# PowerTestbenchBoard.net
KiCad netlist of a schematic drawn in EAGLE
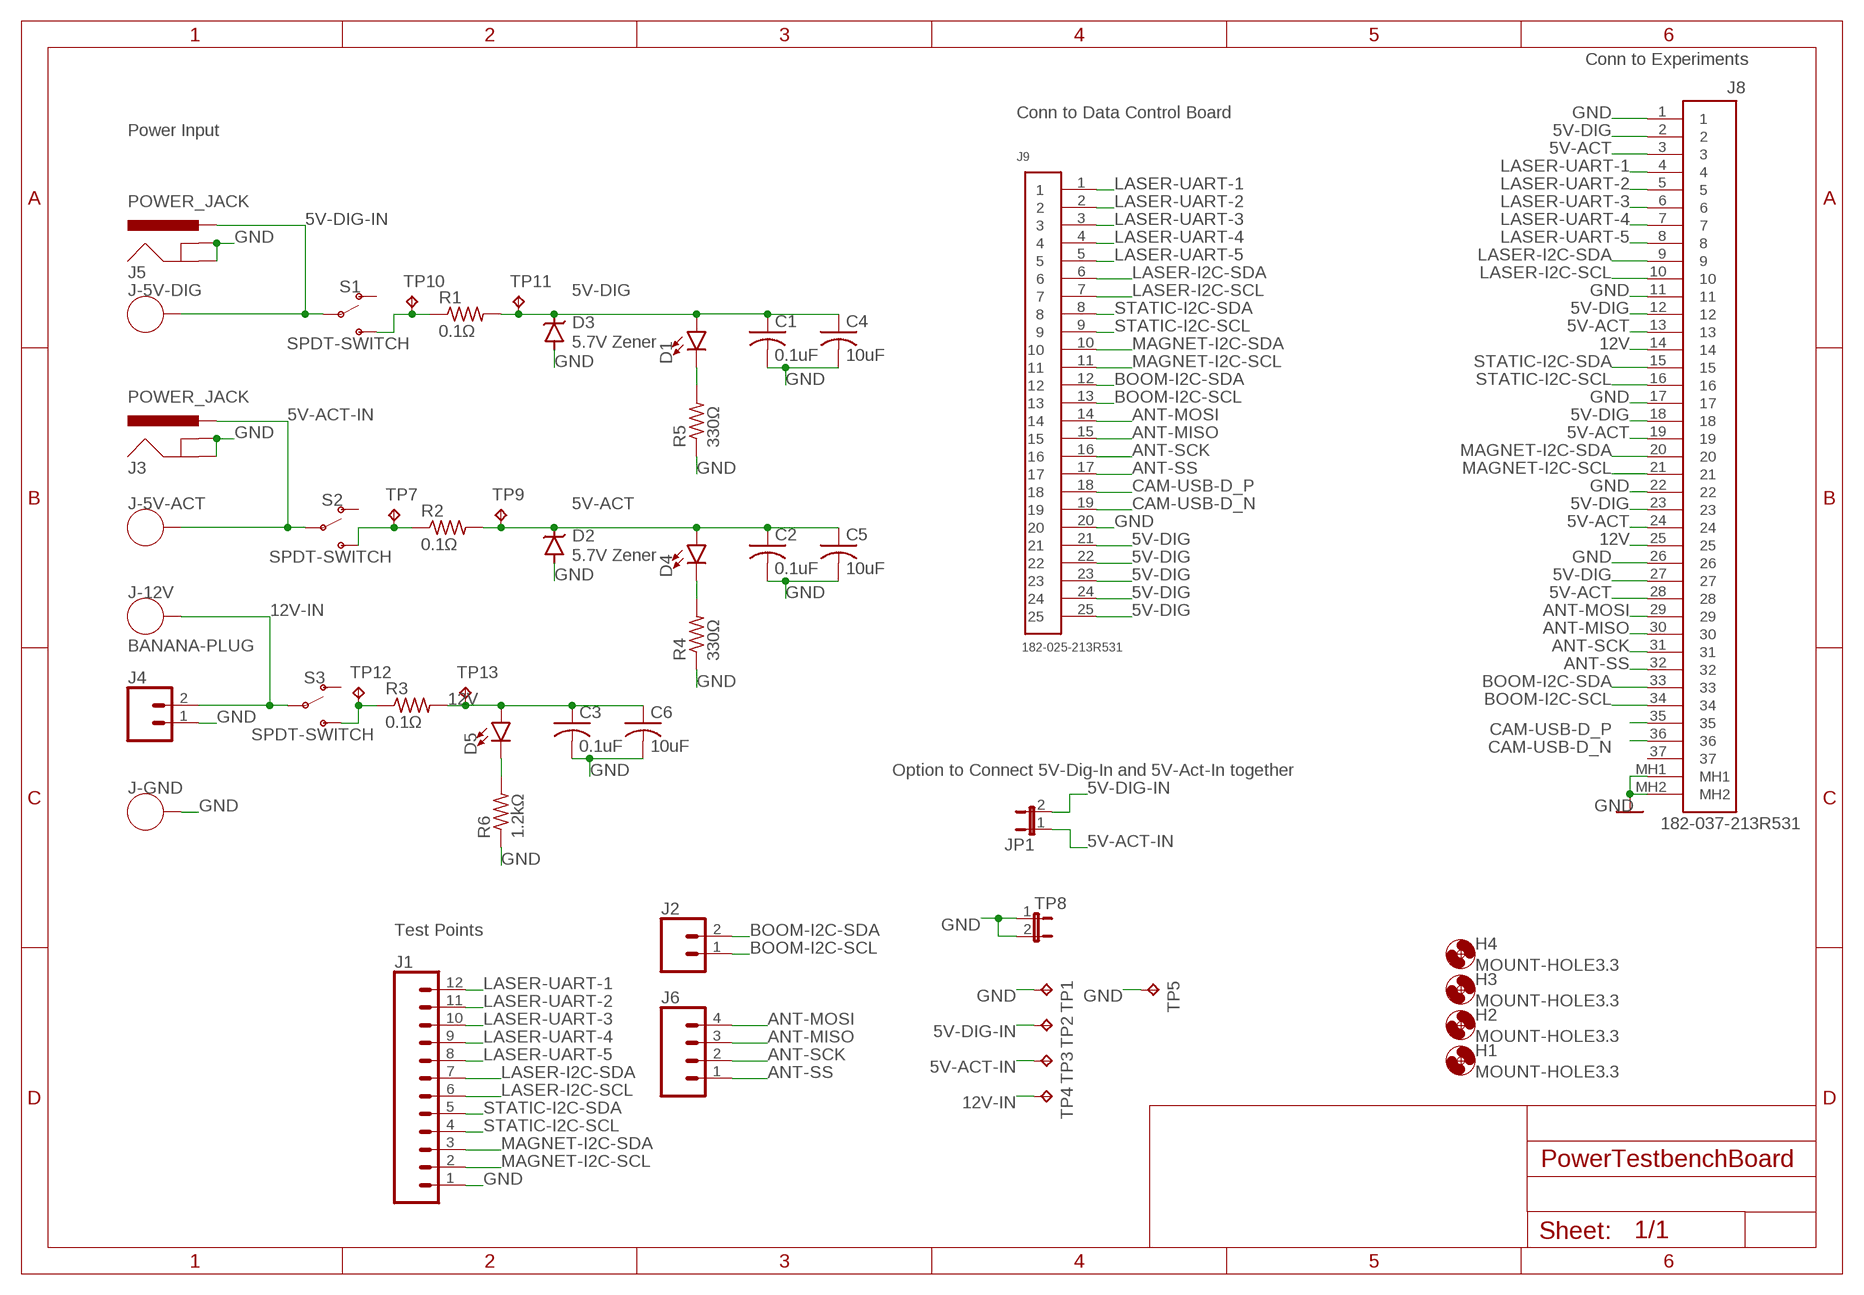
[diagram p0: schematic, sheet 1]

(export (version "E")
  (design (tool "Eeschema 10.0.6"))
  (components
    (comp (ref "C1")
      (value "0.1uF")
      (footprint "eagle-import:C0805")
      (libsource (lib "eagle-import") (part "C-USC0805"))
    )
    (comp (ref "C2")
      (value "0.1uF")
      (footprint "eagle-import:C0805")
      (libsource (lib "eagle-import") (part "C-USC0805"))
    )
    (comp (ref "C3")
      (value "0.1uF")
      (footprint "eagle-import:C0805")
      (libsource (lib "eagle-import") (part "C-USC0805"))
    )
    (comp (ref "C4")
      (value "10uF")
      (footprint "eagle-import:C0805")
      (libsource (lib "eagle-import") (part "C-USC0805"))
    )
    (comp (ref "C5")
      (value "10uF")
      (footprint "eagle-import:C0805")
      (libsource (lib "eagle-import") (part "C-USC0805"))
    )
    (comp (ref "C6")
      (value "10uF")
      (footprint "eagle-import:C0805")
      (libsource (lib "eagle-import") (part "C-USC0805"))
    )
    (comp (ref "D1")
      (value "LED-3MM-NO_SILK")
      (footprint "eagle-import:LED_3MM-NS")
      (libsource (lib "eagle-import") (part "LED-3MM-NO_SILK"))
    )
    (comp (ref "D2")
      (value "5.7V Zener")
      (footprint "eagle-import:SMB")
      (libsource (lib "eagle-import") (part "ZENER-GENERICSMB"))
    )
    (comp (ref "D3")
      (value "5.7V Zener")
      (footprint "eagle-import:SMB")
      (libsource (lib "eagle-import") (part "ZENER-GENERICSMB"))
    )
    (comp (ref "D4")
      (value "LED-3MM-NO_SILK")
      (footprint "eagle-import:LED_3MM-NS")
      (libsource (lib "eagle-import") (part "LED-3MM-NO_SILK"))
    )
    (comp (ref "D5")
      (value "LED-3MM-NO_SILK")
      (footprint "eagle-import:LED_3MM-NS")
      (libsource (lib "eagle-import") (part "LED-3MM-NO_SILK"))
    )
    (comp (ref "H1")
      (value "MOUNT-HOLE3.3")
      (footprint "eagle-import:3,3")
      (libsource (lib "eagle-import") (part "MOUNT-HOLE3.3"))
    )
    (comp (ref "H2")
      (value "MOUNT-HOLE3.3")
      (footprint "eagle-import:3,3")
      (libsource (lib "eagle-import") (part "MOUNT-HOLE3.3"))
    )
    (comp (ref "H3")
      (value "MOUNT-HOLE3.3")
      (footprint "eagle-import:3,3")
      (libsource (lib "eagle-import") (part "MOUNT-HOLE3.3"))
    )
    (comp (ref "H4")
      (value "MOUNT-HOLE3.3")
      (footprint "eagle-import:3,3")
      (libsource (lib "eagle-import") (part "MOUNT-HOLE3.3"))
    )
    (comp (ref "J-5V-ACT")
      (value "BANANA-PLUG")
      (footprint "eagle-import:BANANA-JACK")
      (libsource (lib "eagle-import") (part "BANANA-PLUG"))
    )
    (comp (ref "J-5V-DIG")
      (value "BANANA-PLUG")
      (footprint "eagle-import:BANANA-JACK")
      (libsource (lib "eagle-import") (part "BANANA-PLUG"))
    )
    (comp (ref "J-12V")
      (value "BANANA-PLUG")
      (footprint "eagle-import:BANANA-JACK")
      (libsource (lib "eagle-import") (part "BANANA-PLUG"))
    )
    (comp (ref "J-GND")
      (value "BANANA-PLUG")
      (footprint "eagle-import:BANANA-JACK")
      (libsource (lib "eagle-import") (part "BANANA-PLUG"))
    )
    (comp (ref "J1")
      (value "CONN_12")
      (footprint "eagle-import:1X12")
      (libsource (lib "eagle-import") (part "CONN_12"))
    )
    (comp (ref "J2")
      (value "CONN_02")
      (footprint "eagle-import:1X02")
      (libsource (lib "eagle-import") (part "CONN_02"))
    )
    (comp (ref "J3")
      (value "POWER_JACK")
      (footprint "eagle-import:POWER_JACK_PTH")
      (libsource (lib "eagle-import") (part "POWER_JACK"))
    )
    (comp (ref "J4")
      (value "CONN_023.5MM")
      (footprint "eagle-import:SCREWTERMINAL-3.5MM-2")
      (libsource (lib "eagle-import") (part "CONN_023.5MM"))
    )
    (comp (ref "J5")
      (value "POWER_JACK")
      (footprint "eagle-import:POWER_JACK_PTH")
      (libsource (lib "eagle-import") (part "POWER_JACK"))
    )
    (comp (ref "J6")
      (value "CONN_04")
      (footprint "eagle-import:1X04")
      (libsource (lib "eagle-import") (part "CONN_04"))
    )
    (comp (ref "J8")
      (value "182-037-213R531")
      (footprint "eagle-import:182-037-213R531")
      (fields
        (field (name "DIGI_KEY_PART_NUMBER") "182-37FE-ND")
        (field (name "MANUFACTURER") "NorComp Inc.")
        (field (name "CREATED_BY") "PCBLayout.com")
      )
      (libsource (lib "eagle-import") (part "182-037-213R531"))
    )
    (comp (ref "J9")
      (value "182-025-213R531")
      (footprint "eagle-import:182-025-213R531")
      (fields
        (field (name "DIGIKEY_PART_NO") "182-25FE-ND")
        (field (name "MANUFACTURER") "NorComp Inc.")
        (field (name "CREATED_BY") "PCBLayout.com")
      )
      (libsource (lib "eagle-import") (part "182-025-213R531"))
    )
    (comp (ref "JP1")
      (value "JP1E")
      (footprint "eagle-import:JP1")
      (libsource (lib "eagle-import") (part "JP1E"))
    )
    (comp (ref "R1")
      (value "0.1Ω")
      (footprint "eagle-import:R1206")
      (libsource (lib "eagle-import") (part "R-US_R1206"))
    )
    (comp (ref "R2")
      (value "0.1Ω")
      (footprint "eagle-import:R1206")
      (libsource (lib "eagle-import") (part "R-US_R1206"))
    )
    (comp (ref "R3")
      (value "0.1Ω")
      (footprint "eagle-import:R1206")
      (libsource (lib "eagle-import") (part "R-US_R1206"))
    )
    (comp (ref "R4")
      (value "330Ω")
      (footprint "eagle-import:R0805")
      (libsource (lib "eagle-import") (part "R-US_R0805"))
    )
    (comp (ref "R5")
      (value "330Ω")
      (footprint "eagle-import:R0805")
      (libsource (lib "eagle-import") (part "R-US_R0805"))
    )
    (comp (ref "R6")
      (value "1.2kΩ")
      (footprint "eagle-import:R0805")
      (libsource (lib "eagle-import") (part "R-US_R0805"))
    )
    (comp (ref "S1")
      (value "SPDT-SWITCH")
      (footprint "eagle-import:SWITCH_SPDT_PTH_11.6X4.0MM")
      (libsource (lib "eagle-import") (part "SPDT-SWITCH"))
    )
    (comp (ref "S2")
      (value "SPDT-SWITCH")
      (footprint "eagle-import:SWITCH_SPDT_PTH_11.6X4.0MM")
      (libsource (lib "eagle-import") (part "SPDT-SWITCH"))
    )
    (comp (ref "S3")
      (value "SPDT-SWITCH")
      (footprint "eagle-import:SWITCH_SPDT_PTH_11.6X4.0MM")
      (libsource (lib "eagle-import") (part "SPDT-SWITCH"))
    )
    (comp (ref "TP1")
      (value "TPPAD1-13")
      (footprint "eagle-import:P1-13")
      (libsource (lib "eagle-import") (part "TPPAD1-13"))
    )
    (comp (ref "TP2")
      (value "TPPAD1-13")
      (footprint "eagle-import:P1-13")
      (libsource (lib "eagle-import") (part "TPPAD1-13"))
    )
    (comp (ref "TP3")
      (value "TPPAD1-13")
      (footprint "eagle-import:P1-13")
      (libsource (lib "eagle-import") (part "TPPAD1-13"))
    )
    (comp (ref "TP4")
      (value "TPPAD1-13")
      (footprint "eagle-import:P1-13")
      (libsource (lib "eagle-import") (part "TPPAD1-13"))
    )
    (comp (ref "TP5")
      (value "TPPAD1-13")
      (footprint "eagle-import:P1-13")
      (libsource (lib "eagle-import") (part "TPPAD1-13"))
    )
    (comp (ref "TP7")
      (value "TPPAD1-13")
      (footprint "eagle-import:P1-13")
      (libsource (lib "eagle-import") (part "TPPAD1-13"))
    )
    (comp (ref "TP8")
      (value "JP1E")
      (footprint "eagle-import:JP1")
      (libsource (lib "eagle-import") (part "JP1E"))
    )
    (comp (ref "TP9")
      (value "TPPAD1-13")
      (footprint "eagle-import:P1-13")
      (libsource (lib "eagle-import") (part "TPPAD1-13"))
    )
    (comp (ref "TP10")
      (value "TPPAD1-13")
      (footprint "eagle-import:P1-13")
      (libsource (lib "eagle-import") (part "TPPAD1-13"))
    )
    (comp (ref "TP11")
      (value "TPPAD1-13")
      (footprint "eagle-import:P1-13")
      (libsource (lib "eagle-import") (part "TPPAD1-13"))
    )
    (comp (ref "TP12")
      (value "TPPAD1-13")
      (footprint "eagle-import:P1-13")
      (libsource (lib "eagle-import") (part "TPPAD1-13"))
    )
    (comp (ref "TP13")
      (value "TPPAD1-13")
      (footprint "eagle-import:P1-13")
      (libsource (lib "eagle-import") (part "TPPAD1-13"))
    )
  )
  (nets
    (net (code "1") (name "/5V-ACT") (class "Default")
      (node (ref "C2") (pin "1") (pinfunction "1_1") (pintype "passive"))
      (node (ref "C5") (pin "1") (pinfunction "1_1") (pintype "passive"))
      (node (ref "D2") (pin "C") (pinfunction "C_C") (pintype "passive"))
      (node (ref "D4") (pin "A") (pinfunction "A_A") (pintype "passive"))
      (node (ref "J8") (pin "13") (pinfunction "13_13") (pintype "passive"))
      (node (ref "J8") (pin "19") (pinfunction "19_19") (pintype "passive"))
      (node (ref "J8") (pin "24") (pinfunction "24_24") (pintype "passive"))
      (node (ref "J8") (pin "28") (pinfunction "28_28") (pintype "passive"))
      (node (ref "J8") (pin "3") (pinfunction "3_3") (pintype "passive"))
      (node (ref "R2") (pin "2") (pinfunction "2_2") (pintype "passive"))
      (node (ref "TP9") (pin "TP") (pinfunction "TP_TP") (pintype "input"))
    )
    (net (code "2") (name "/5V-ACT-IN") (class "Default")
      (node (ref "J-5V-ACT") (pin "P$1") (pinfunction "P$1_P$1") (pintype "bidirectional"))
      (node (ref "J-5V-ACT") (pin "P$2") (pinfunction "P$1_P$2") (pintype "bidirectional"))
      (node (ref "J3") (pin "PWR") (pinfunction "PWR_PWR") (pintype "bidirectional"))
      (node (ref "JP1") (pin "1") (pinfunction "1_1") (pintype "passive"))
      (node (ref "S2") (pin "2") (pinfunction "P_2") (pintype "passive"))
      (node (ref "TP3") (pin "TP") (pinfunction "TP_TP") (pintype "input"))
    )
    (net (code "3") (name "/5V-DIG") (class "Default")
      (node (ref "C1") (pin "1") (pinfunction "1_1") (pintype "passive"))
      (node (ref "C4") (pin "1") (pinfunction "1_1") (pintype "passive"))
      (node (ref "D1") (pin "A") (pinfunction "A_A") (pintype "passive"))
      (node (ref "D3") (pin "C") (pinfunction "C_C") (pintype "passive"))
      (node (ref "J8") (pin "12") (pinfunction "12_12") (pintype "passive"))
      (node (ref "J8") (pin "18") (pinfunction "18_18") (pintype "passive"))
      (node (ref "J8") (pin "2") (pinfunction "2_2") (pintype "passive"))
      (node (ref "J8") (pin "23") (pinfunction "23_23") (pintype "passive"))
      (node (ref "J8") (pin "27") (pinfunction "27_27") (pintype "passive"))
      (node (ref "J9") (pin "21") (pinfunction "21_21") (pintype "passive"))
      (node (ref "J9") (pin "22") (pinfunction "22_22") (pintype "passive"))
      (node (ref "J9") (pin "23") (pinfunction "23_23") (pintype "passive"))
      (node (ref "J9") (pin "24") (pinfunction "24_24") (pintype "passive"))
      (node (ref "J9") (pin "25") (pinfunction "25_25") (pintype "passive"))
      (node (ref "R1") (pin "2") (pinfunction "2_2") (pintype "passive"))
      (node (ref "TP11") (pin "TP") (pinfunction "TP_TP") (pintype "input"))
    )
    (net (code "4") (name "/5V-DIG-IN") (class "Default")
      (node (ref "J-5V-DIG") (pin "P$1") (pinfunction "P$1_P$1") (pintype "bidirectional"))
      (node (ref "J-5V-DIG") (pin "P$2") (pinfunction "P$1_P$2") (pintype "bidirectional"))
      (node (ref "J5") (pin "PWR") (pinfunction "PWR_PWR") (pintype "bidirectional"))
      (node (ref "JP1") (pin "2") (pinfunction "2_2") (pintype "passive"))
      (node (ref "S1") (pin "2") (pinfunction "P_2") (pintype "passive"))
      (node (ref "TP2") (pin "TP") (pinfunction "TP_TP") (pintype "input"))
    )
    (net (code "5") (name "/12V") (class "Default")
      (node (ref "C3") (pin "1") (pinfunction "1_1") (pintype "passive"))
      (node (ref "C6") (pin "1") (pinfunction "1_1") (pintype "passive"))
      (node (ref "D5") (pin "A") (pinfunction "A_A") (pintype "passive"))
      (node (ref "J8") (pin "14") (pinfunction "14_14") (pintype "passive"))
      (node (ref "J8") (pin "25") (pinfunction "25_25") (pintype "passive"))
      (node (ref "R3") (pin "2") (pinfunction "2_2") (pintype "passive"))
      (node (ref "TP13") (pin "TP") (pinfunction "TP_TP") (pintype "input"))
    )
    (net (code "6") (name "/12V-IN") (class "Default")
      (node (ref "J-12V") (pin "P$1") (pinfunction "P$1_P$1") (pintype "bidirectional"))
      (node (ref "J-12V") (pin "P$2") (pinfunction "P$1_P$2") (pintype "bidirectional"))
      (node (ref "J4") (pin "2") (pinfunction "2_2") (pintype "passive"))
      (node (ref "S3") (pin "2") (pinfunction "P_2") (pintype "passive"))
      (node (ref "TP4") (pin "TP") (pinfunction "TP_TP") (pintype "input"))
    )
    (net (code "7") (name "/ANT-MISO") (class "Default")
      (node (ref "J6") (pin "3") (pinfunction "3_3") (pintype "passive"))
      (node (ref "J8") (pin "30") (pinfunction "30_30") (pintype "passive"))
      (node (ref "J9") (pin "15") (pinfunction "15_15") (pintype "passive"))
    )
    (net (code "8") (name "/ANT-MOSI") (class "Default")
      (node (ref "J6") (pin "4") (pinfunction "4_4") (pintype "passive"))
      (node (ref "J8") (pin "29") (pinfunction "29_29") (pintype "passive"))
      (node (ref "J9") (pin "14") (pinfunction "14_14") (pintype "passive"))
    )
    (net (code "9") (name "/ANT-SCK") (class "Default")
      (node (ref "J6") (pin "2") (pinfunction "2_2") (pintype "passive"))
      (node (ref "J8") (pin "31") (pinfunction "31_31") (pintype "passive"))
      (node (ref "J9") (pin "16") (pinfunction "16_16") (pintype "passive"))
    )
    (net (code "10") (name "/ANT-SS") (class "Default")
      (node (ref "J6") (pin "1") (pinfunction "1_1") (pintype "passive"))
      (node (ref "J8") (pin "32") (pinfunction "32_32") (pintype "passive"))
      (node (ref "J9") (pin "17") (pinfunction "17_17") (pintype "passive"))
    )
    (net (code "11") (name "/BOOM-I2C-SCL") (class "Default")
      (node (ref "J2") (pin "1") (pinfunction "1_1") (pintype "passive"))
      (node (ref "J8") (pin "34") (pinfunction "34_34") (pintype "passive"))
      (node (ref "J9") (pin "13") (pinfunction "13_13") (pintype "passive"))
    )
    (net (code "12") (name "/BOOM-I2C-SDA") (class "Default")
      (node (ref "J2") (pin "2") (pinfunction "2_2") (pintype "passive"))
      (node (ref "J8") (pin "33") (pinfunction "33_33") (pintype "passive"))
      (node (ref "J9") (pin "12") (pinfunction "12_12") (pintype "passive"))
    )
    (net (code "13") (name "/CAM-USB-D_N") (class "Default")
      (node (ref "J8") (pin "36") (pinfunction "36_36") (pintype "passive"))
      (node (ref "J9") (pin "19") (pinfunction "19_19") (pintype "passive"))
    )
    (net (code "14") (name "/CAM-USB-D_P") (class "Default")
      (node (ref "J8") (pin "35") (pinfunction "35_35") (pintype "passive"))
      (node (ref "J9") (pin "18") (pinfunction "18_18") (pintype "passive"))
    )
    (net (code "15") (name "/LASER-I2C-SCL") (class "Default")
      (node (ref "J1") (pin "6") (pinfunction "6_6") (pintype "passive"))
      (node (ref "J8") (pin "10") (pinfunction "10_10") (pintype "passive"))
      (node (ref "J9") (pin "7") (pinfunction "7_7") (pintype "passive"))
    )
    (net (code "16") (name "/LASER-I2C-SDA") (class "Default")
      (node (ref "J1") (pin "7") (pinfunction "7_7") (pintype "passive"))
      (node (ref "J8") (pin "9") (pinfunction "9_9") (pintype "passive"))
      (node (ref "J9") (pin "6") (pinfunction "6_6") (pintype "passive"))
    )
    (net (code "17") (name "/LASER-UART-1") (class "Default")
      (node (ref "J1") (pin "12") (pinfunction "12_12") (pintype "passive"))
      (node (ref "J8") (pin "4") (pinfunction "4_4") (pintype "passive"))
      (node (ref "J9") (pin "1") (pinfunction "1_1") (pintype "passive"))
    )
    (net (code "18") (name "/LASER-UART-2") (class "Default")
      (node (ref "J1") (pin "11") (pinfunction "11_11") (pintype "passive"))
      (node (ref "J8") (pin "5") (pinfunction "5_5") (pintype "passive"))
      (node (ref "J9") (pin "2") (pinfunction "2_2") (pintype "passive"))
    )
    (net (code "19") (name "/LASER-UART-3") (class "Default")
      (node (ref "J1") (pin "10") (pinfunction "10_10") (pintype "passive"))
      (node (ref "J8") (pin "6") (pinfunction "6_6") (pintype "passive"))
      (node (ref "J9") (pin "3") (pinfunction "3_3") (pintype "passive"))
    )
    (net (code "20") (name "/LASER-UART-4") (class "Default")
      (node (ref "J1") (pin "9") (pinfunction "9_9") (pintype "passive"))
      (node (ref "J8") (pin "7") (pinfunction "7_7") (pintype "passive"))
      (node (ref "J9") (pin "4") (pinfunction "4_4") (pintype "passive"))
    )
    (net (code "21") (name "/LASER-UART-5") (class "Default")
      (node (ref "J1") (pin "8") (pinfunction "8_8") (pintype "passive"))
      (node (ref "J8") (pin "8") (pinfunction "8_8") (pintype "passive"))
      (node (ref "J9") (pin "5") (pinfunction "5_5") (pintype "passive"))
    )
    (net (code "22") (name "/MAGNET-I2C-SCL") (class "Default")
      (node (ref "J1") (pin "2") (pinfunction "2_2") (pintype "passive"))
      (node (ref "J8") (pin "21") (pinfunction "21_21") (pintype "passive"))
      (node (ref "J9") (pin "11") (pinfunction "11_11") (pintype "passive"))
    )
    (net (code "23") (name "/MAGNET-I2C-SDA") (class "Default")
      (node (ref "J1") (pin "3") (pinfunction "3_3") (pintype "passive"))
      (node (ref "J8") (pin "20") (pinfunction "20_20") (pintype "passive"))
      (node (ref "J9") (pin "10") (pinfunction "10_10") (pintype "passive"))
    )
    (net (code "24") (name "/STATIC-I2C-SCL") (class "Default")
      (node (ref "J1") (pin "4") (pinfunction "4_4") (pintype "passive"))
      (node (ref "J8") (pin "16") (pinfunction "16_16") (pintype "passive"))
      (node (ref "J9") (pin "9") (pinfunction "9_9") (pintype "passive"))
    )
    (net (code "25") (name "/STATIC-I2C-SDA") (class "Default")
      (node (ref "J1") (pin "5") (pinfunction "5_5") (pintype "passive"))
      (node (ref "J8") (pin "15") (pinfunction "15_15") (pintype "passive"))
      (node (ref "J9") (pin "8") (pinfunction "8_8") (pintype "passive"))
    )
    (net (code "26") (name "GND") (class "Default")
      (node (ref "C1") (pin "2") (pinfunction "2_2") (pintype "passive"))
      (node (ref "C2") (pin "2") (pinfunction "2_2") (pintype "passive"))
      (node (ref "C3") (pin "2") (pinfunction "2_2") (pintype "passive"))
      (node (ref "C4") (pin "2") (pinfunction "2_2") (pintype "passive"))
      (node (ref "C5") (pin "2") (pinfunction "2_2") (pintype "passive"))
      (node (ref "C6") (pin "2") (pinfunction "2_2") (pintype "passive"))
      (node (ref "D2") (pin "A") (pinfunction "A_A") (pintype "passive"))
      (node (ref "D3") (pin "A") (pinfunction "A_A") (pintype "passive"))
      (node (ref "J-GND") (pin "P$1") (pinfunction "P$1_P$1") (pintype "bidirectional"))
      (node (ref "J-GND") (pin "P$2") (pinfunction "P$1_P$2") (pintype "bidirectional"))
      (node (ref "J1") (pin "1") (pinfunction "1_1") (pintype "passive"))
      (node (ref "J3") (pin "GND") (pinfunction "GND_GND") (pintype "bidirectional"))
      (node (ref "J3") (pin "GNDBREAK") (pinfunction "GNDBREAK_GNDBREAK") (pintype "bidirectional"))
      (node (ref "J4") (pin "1") (pinfunction "1_1") (pintype "passive"))
      (node (ref "J5") (pin "GND") (pinfunction "GND_GND") (pintype "bidirectional"))
      (node (ref "J5") (pin "GNDBREAK") (pinfunction "GNDBREAK_GNDBREAK") (pintype "bidirectional"))
      (node (ref "J8") (pin "1") (pinfunction "1_1") (pintype "passive"))
      (node (ref "J8") (pin "11") (pinfunction "11_11") (pintype "passive"))
      (node (ref "J8") (pin "17") (pinfunction "17_17") (pintype "passive"))
      (node (ref "J8") (pin "22") (pinfunction "22_22") (pintype "passive"))
      (node (ref "J8") (pin "26") (pinfunction "26_26") (pintype "passive"))
      (node (ref "J8") (pin "MH1") (pinfunction "MH1_MH1") (pintype "passive"))
      (node (ref "J8") (pin "MH2") (pinfunction "MH2_MH2") (pintype "passive"))
      (node (ref "J9") (pin "20") (pinfunction "20_20") (pintype "passive"))
      (node (ref "R4") (pin "1") (pinfunction "1_1") (pintype "passive"))
      (node (ref "R5") (pin "1") (pinfunction "1_1") (pintype "passive"))
      (node (ref "R6") (pin "1") (pinfunction "1_1") (pintype "passive"))
      (node (ref "TP1") (pin "TP") (pinfunction "TP_TP") (pintype "input"))
      (node (ref "TP5") (pin "TP") (pinfunction "TP_TP") (pintype "input"))
      (node (ref "TP8") (pin "1") (pinfunction "1_1") (pintype "passive"))
      (node (ref "TP8") (pin "2") (pinfunction "2_2") (pintype "passive"))
    )
    (net (code "27") (name "Net-(D1-C)") (class "Default")
      (node (ref "D1") (pin "K") (pinfunction "C_K") (pintype "passive"))
      (node (ref "R5") (pin "2") (pinfunction "2_2") (pintype "passive"))
    )
    (net (code "28") (name "Net-(D4-C)") (class "Default")
      (node (ref "D4") (pin "K") (pinfunction "C_K") (pintype "passive"))
      (node (ref "R4") (pin "2") (pinfunction "2_2") (pintype "passive"))
    )
    (net (code "29") (name "Net-(D5-C)") (class "Default")
      (node (ref "D5") (pin "K") (pinfunction "C_K") (pintype "passive"))
      (node (ref "R6") (pin "2") (pinfunction "2_2") (pintype "passive"))
    )
    (net (code "30") (name "Net-(S1-S)") (class "Default")
      (node (ref "R1") (pin "1") (pinfunction "1_1") (pintype "passive"))
      (node (ref "S1") (pin "1") (pinfunction "S_1") (pintype "passive"))
      (node (ref "TP10") (pin "TP") (pinfunction "TP_TP") (pintype "input"))
    )
    (net (code "31") (name "Net-(S2-S)") (class "Default")
      (node (ref "R2") (pin "1") (pinfunction "1_1") (pintype "passive"))
      (node (ref "S2") (pin "1") (pinfunction "S_1") (pintype "passive"))
      (node (ref "TP7") (pin "TP") (pinfunction "TP_TP") (pintype "input"))
    )
    (net (code "32") (name "Net-(S3-S)") (class "Default")
      (node (ref "R3") (pin "1") (pinfunction "1_1") (pintype "passive"))
      (node (ref "S3") (pin "1") (pinfunction "S_1") (pintype "passive"))
      (node (ref "TP12") (pin "TP") (pinfunction "TP_TP") (pintype "input"))
    )
    (net (code "33") (name "unconnected-(J8-Pad37)") (class "Default")
      (node (ref "J8") (pin "37") (pinfunction "37_37") (pintype "passive"))
    )
    (net (code "34") (name "unconnected-(S1-O-Pad3)") (class "Default")
      (node (ref "S1") (pin "3") (pinfunction "O_3") (pintype "passive"))
    )
    (net (code "35") (name "unconnected-(S2-O-Pad3)") (class "Default")
      (node (ref "S2") (pin "3") (pinfunction "O_3") (pintype "passive"))
    )
    (net (code "36") (name "unconnected-(S3-O-Pad3)") (class "Default")
      (node (ref "S3") (pin "3") (pinfunction "O_3") (pintype "passive"))
    )
  )
)
